# right.net
KiCad netlist of a schematic drawn in EAGLE
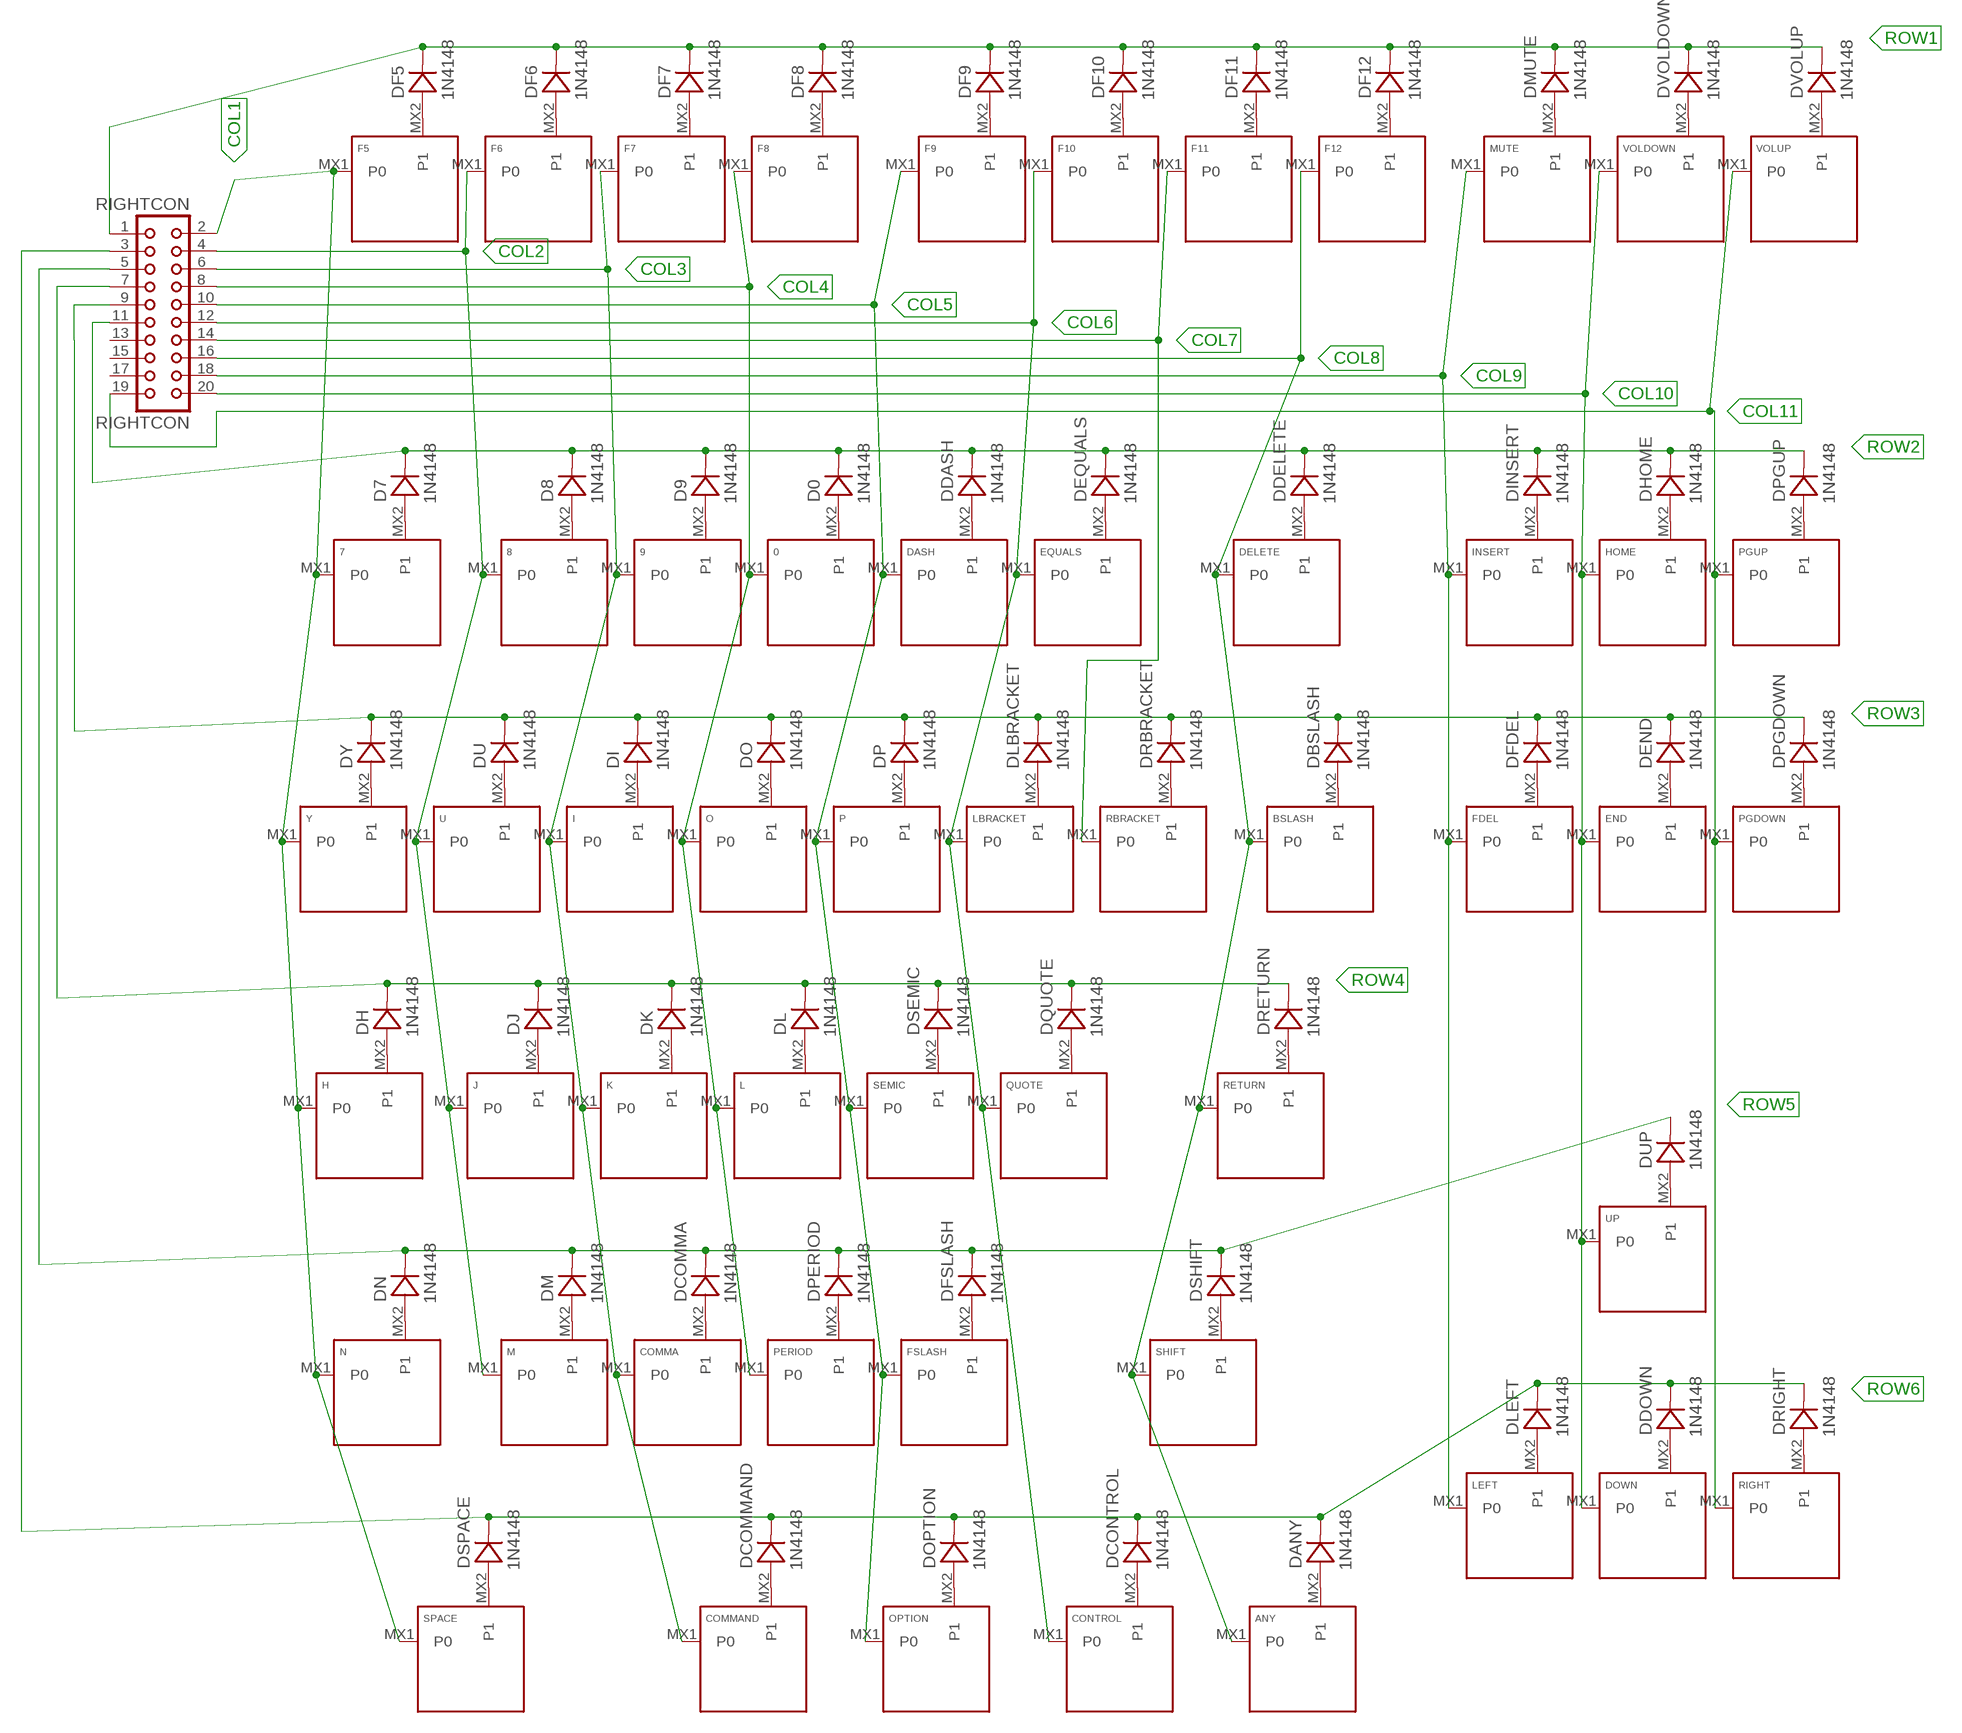
[diagram p0: schematic, sheet 1]

(export (version "E")
  (design (tool "Eeschema 10.0.6"))
  (components
    (comp (ref "0")
      (value "KEYSWITCH-PLAIN-MX-1U")
      (footprint "eagle-import:MX-1U")
      (libsource (lib "eagle-import") (part "KEYSWITCH-PLAIN-MX-1U"))
    )
    (comp (ref "7")
      (value "KEYSWITCH-PLAIN-MX-1U")
      (footprint "eagle-import:MX-1U")
      (libsource (lib "eagle-import") (part "KEYSWITCH-PLAIN-MX-1U"))
    )
    (comp (ref "8")
      (value "KEYSWITCH-PLAIN-MX-1U")
      (footprint "eagle-import:MX-1U")
      (libsource (lib "eagle-import") (part "KEYSWITCH-PLAIN-MX-1U"))
    )
    (comp (ref "9")
      (value "KEYSWITCH-PLAIN-MX-1U")
      (footprint "eagle-import:MX-1U")
      (libsource (lib "eagle-import") (part "KEYSWITCH-PLAIN-MX-1U"))
    )
    (comp (ref "ANY")
      (value "KEYSWITCH-PLAIN-MX-1U")
      (footprint "eagle-import:MX-1U")
      (libsource (lib "eagle-import") (part "KEYSWITCH-PLAIN-MX-1U"))
    )
    (comp (ref "BSLASH")
      (value "KEYSWITCH-PLAIN-MX-1U")
      (footprint "eagle-import:MX-1U")
      (libsource (lib "eagle-import") (part "KEYSWITCH-PLAIN-MX-1U"))
    )
    (comp (ref "COMMA")
      (value "KEYSWITCH-PLAIN-MX-1U")
      (footprint "eagle-import:MX-1U")
      (libsource (lib "eagle-import") (part "KEYSWITCH-PLAIN-MX-1U"))
    )
    (comp (ref "COMMAND")
      (value "KEYSWITCH-PLAIN-MX-1U")
      (footprint "eagle-import:MX-1U")
      (libsource (lib "eagle-import") (part "KEYSWITCH-PLAIN-MX-1U"))
    )
    (comp (ref "CONTROL")
      (value "KEYSWITCH-PLAIN-MX-1U")
      (footprint "eagle-import:MX-1U")
      (libsource (lib "eagle-import") (part "KEYSWITCH-PLAIN-MX-1U"))
    )
    (comp (ref "D0")
      (value "1N4148")
      (footprint "eagle-import:DO-35")
      (libsource (lib "eagle-import") (part "DIODE-DO-35"))
    )
    (comp (ref "D7")
      (value "1N4148")
      (footprint "eagle-import:DO-35")
      (libsource (lib "eagle-import") (part "DIODE-DO-35"))
    )
    (comp (ref "D8")
      (value "1N4148")
      (footprint "eagle-import:DO-35")
      (libsource (lib "eagle-import") (part "DIODE-DO-35"))
    )
    (comp (ref "D9")
      (value "1N4148")
      (footprint "eagle-import:DO-35")
      (libsource (lib "eagle-import") (part "DIODE-DO-35"))
    )
    (comp (ref "DANY")
      (value "1N4148")
      (footprint "eagle-import:DO-35")
      (libsource (lib "eagle-import") (part "DIODE-DO-35"))
    )
    (comp (ref "DASH")
      (value "KEYSWITCH-PLAIN-MX-1U")
      (footprint "eagle-import:MX-1U")
      (libsource (lib "eagle-import") (part "KEYSWITCH-PLAIN-MX-1U"))
    )
    (comp (ref "DBSLASH")
      (value "1N4148")
      (footprint "eagle-import:DO-35")
      (libsource (lib "eagle-import") (part "DIODE-DO-35"))
    )
    (comp (ref "DCOMMA")
      (value "1N4148")
      (footprint "eagle-import:DO-35")
      (libsource (lib "eagle-import") (part "DIODE-DO-35"))
    )
    (comp (ref "DCOMMAND")
      (value "1N4148")
      (footprint "eagle-import:DO-35")
      (libsource (lib "eagle-import") (part "DIODE-DO-35"))
    )
    (comp (ref "DCONTROL")
      (value "1N4148")
      (footprint "eagle-import:DO-35")
      (libsource (lib "eagle-import") (part "DIODE-DO-35"))
    )
    (comp (ref "DDASH")
      (value "1N4148")
      (footprint "eagle-import:DO-35")
      (libsource (lib "eagle-import") (part "DIODE-DO-35"))
    )
    (comp (ref "DDELETE")
      (value "1N4148")
      (footprint "eagle-import:DO-35")
      (libsource (lib "eagle-import") (part "DIODE-DO-35"))
    )
    (comp (ref "DDOWN")
      (value "1N4148")
      (footprint "eagle-import:DO-35")
      (libsource (lib "eagle-import") (part "DIODE-DO-35"))
    )
    (comp (ref "DELETE")
      (value "KEYSWITCH-PLAIN-MX-2U")
      (footprint "eagle-import:MX-2U")
      (libsource (lib "eagle-import") (part "KEYSWITCH-PLAIN-MX-2U"))
    )
    (comp (ref "DEND")
      (value "1N4148")
      (footprint "eagle-import:DO-35")
      (libsource (lib "eagle-import") (part "DIODE-DO-35"))
    )
    (comp (ref "DEQUALS")
      (value "1N4148")
      (footprint "eagle-import:DO-35")
      (libsource (lib "eagle-import") (part "DIODE-DO-35"))
    )
    (comp (ref "DF5")
      (value "1N4148")
      (footprint "eagle-import:DO-35")
      (libsource (lib "eagle-import") (part "DIODE-DO-35"))
    )
    (comp (ref "DF6")
      (value "1N4148")
      (footprint "eagle-import:DO-35")
      (libsource (lib "eagle-import") (part "DIODE-DO-35"))
    )
    (comp (ref "DF7")
      (value "1N4148")
      (footprint "eagle-import:DO-35")
      (libsource (lib "eagle-import") (part "DIODE-DO-35"))
    )
    (comp (ref "DF8")
      (value "1N4148")
      (footprint "eagle-import:DO-35")
      (libsource (lib "eagle-import") (part "DIODE-DO-35"))
    )
    (comp (ref "DF9")
      (value "1N4148")
      (footprint "eagle-import:DO-35")
      (libsource (lib "eagle-import") (part "DIODE-DO-35"))
    )
    (comp (ref "DF10")
      (value "1N4148")
      (footprint "eagle-import:DO-35")
      (libsource (lib "eagle-import") (part "DIODE-DO-35"))
    )
    (comp (ref "DF11")
      (value "1N4148")
      (footprint "eagle-import:DO-35")
      (libsource (lib "eagle-import") (part "DIODE-DO-35"))
    )
    (comp (ref "DF12")
      (value "1N4148")
      (footprint "eagle-import:DO-35")
      (libsource (lib "eagle-import") (part "DIODE-DO-35"))
    )
    (comp (ref "DFDEL")
      (value "1N4148")
      (footprint "eagle-import:DO-35")
      (libsource (lib "eagle-import") (part "DIODE-DO-35"))
    )
    (comp (ref "DFSLASH")
      (value "1N4148")
      (footprint "eagle-import:DO-35")
      (libsource (lib "eagle-import") (part "DIODE-DO-35"))
    )
    (comp (ref "DH")
      (value "1N4148")
      (footprint "eagle-import:DO-35")
      (libsource (lib "eagle-import") (part "DIODE-DO-35"))
    )
    (comp (ref "DHOME")
      (value "1N4148")
      (footprint "eagle-import:DO-35")
      (libsource (lib "eagle-import") (part "DIODE-DO-35"))
    )
    (comp (ref "DI")
      (value "1N4148")
      (footprint "eagle-import:DO-35")
      (libsource (lib "eagle-import") (part "DIODE-DO-35"))
    )
    (comp (ref "DINSERT")
      (value "1N4148")
      (footprint "eagle-import:DO-35")
      (libsource (lib "eagle-import") (part "DIODE-DO-35"))
    )
    (comp (ref "DJ")
      (value "1N4148")
      (footprint "eagle-import:DO-35")
      (libsource (lib "eagle-import") (part "DIODE-DO-35"))
    )
    (comp (ref "DK")
      (value "1N4148")
      (footprint "eagle-import:DO-35")
      (libsource (lib "eagle-import") (part "DIODE-DO-35"))
    )
    (comp (ref "DL")
      (value "1N4148")
      (footprint "eagle-import:DO-35")
      (libsource (lib "eagle-import") (part "DIODE-DO-35"))
    )
    (comp (ref "DLBRACKET")
      (value "1N4148")
      (footprint "eagle-import:DO-35")
      (libsource (lib "eagle-import") (part "DIODE-DO-35"))
    )
    (comp (ref "DLEFT")
      (value "1N4148")
      (footprint "eagle-import:DO-35")
      (libsource (lib "eagle-import") (part "DIODE-DO-35"))
    )
    (comp (ref "DM")
      (value "1N4148")
      (footprint "eagle-import:DO-35")
      (libsource (lib "eagle-import") (part "DIODE-DO-35"))
    )
    (comp (ref "DMUTE")
      (value "1N4148")
      (footprint "eagle-import:DO-35")
      (libsource (lib "eagle-import") (part "DIODE-DO-35"))
    )
    (comp (ref "DN")
      (value "1N4148")
      (footprint "eagle-import:DO-35")
      (libsource (lib "eagle-import") (part "DIODE-DO-35"))
    )
    (comp (ref "DO")
      (value "1N4148")
      (footprint "eagle-import:DO-35")
      (libsource (lib "eagle-import") (part "DIODE-DO-35"))
    )
    (comp (ref "DOPTION")
      (value "1N4148")
      (footprint "eagle-import:DO-35")
      (libsource (lib "eagle-import") (part "DIODE-DO-35"))
    )
    (comp (ref "DOWN")
      (value "KEYSWITCH-PLAIN-MX-1U")
      (footprint "eagle-import:MX-1U")
      (libsource (lib "eagle-import") (part "KEYSWITCH-PLAIN-MX-1U"))
    )
    (comp (ref "DP")
      (value "1N4148")
      (footprint "eagle-import:DO-35")
      (libsource (lib "eagle-import") (part "DIODE-DO-35"))
    )
    (comp (ref "DPERIOD")
      (value "1N4148")
      (footprint "eagle-import:DO-35")
      (libsource (lib "eagle-import") (part "DIODE-DO-35"))
    )
    (comp (ref "DPGDOWN")
      (value "1N4148")
      (footprint "eagle-import:DO-35")
      (libsource (lib "eagle-import") (part "DIODE-DO-35"))
    )
    (comp (ref "DPGUP")
      (value "1N4148")
      (footprint "eagle-import:DO-35")
      (libsource (lib "eagle-import") (part "DIODE-DO-35"))
    )
    (comp (ref "DQUOTE")
      (value "1N4148")
      (footprint "eagle-import:DO-35")
      (libsource (lib "eagle-import") (part "DIODE-DO-35"))
    )
    (comp (ref "DRBRACKET")
      (value "1N4148")
      (footprint "eagle-import:DO-35")
      (libsource (lib "eagle-import") (part "DIODE-DO-35"))
    )
    (comp (ref "DRETURN")
      (value "1N4148")
      (footprint "eagle-import:DO-35")
      (libsource (lib "eagle-import") (part "DIODE-DO-35"))
    )
    (comp (ref "DRIGHT")
      (value "1N4148")
      (footprint "eagle-import:DO-35")
      (libsource (lib "eagle-import") (part "DIODE-DO-35"))
    )
    (comp (ref "DSEMIC")
      (value "1N4148")
      (footprint "eagle-import:DO-35")
      (libsource (lib "eagle-import") (part "DIODE-DO-35"))
    )
    (comp (ref "DSHIFT")
      (value "1N4148")
      (footprint "eagle-import:DO-35")
      (libsource (lib "eagle-import") (part "DIODE-DO-35"))
    )
    (comp (ref "DSPACE")
      (value "1N4148")
      (footprint "eagle-import:DO-35")
      (libsource (lib "eagle-import") (part "DIODE-DO-35"))
    )
    (comp (ref "DU")
      (value "1N4148")
      (footprint "eagle-import:DO-35")
      (libsource (lib "eagle-import") (part "DIODE-DO-35"))
    )
    (comp (ref "DUP")
      (value "1N4148")
      (footprint "eagle-import:DO-35")
      (libsource (lib "eagle-import") (part "DIODE-DO-35"))
    )
    (comp (ref "DVOLDOWN")
      (value "1N4148")
      (footprint "eagle-import:DO-35")
      (libsource (lib "eagle-import") (part "DIODE-DO-35"))
    )
    (comp (ref "DVOLUP")
      (value "1N4148")
      (footprint "eagle-import:DO-35")
      (libsource (lib "eagle-import") (part "DIODE-DO-35"))
    )
    (comp (ref "DY")
      (value "1N4148")
      (footprint "eagle-import:DO-35")
      (libsource (lib "eagle-import") (part "DIODE-DO-35"))
    )
    (comp (ref "END")
      (value "KEYSWITCH-PLAIN-MX-1U")
      (footprint "eagle-import:MX-1U")
      (libsource (lib "eagle-import") (part "KEYSWITCH-PLAIN-MX-1U"))
    )
    (comp (ref "EQUALS")
      (value "KEYSWITCH-PLAIN-MX-1U")
      (footprint "eagle-import:MX-1U")
      (libsource (lib "eagle-import") (part "KEYSWITCH-PLAIN-MX-1U"))
    )
    (comp (ref "F5")
      (value "KEYSWITCH-PLAIN-MX-1U")
      (footprint "eagle-import:MX-1U")
      (libsource (lib "eagle-import") (part "KEYSWITCH-PLAIN-MX-1U"))
    )
    (comp (ref "F6")
      (value "KEYSWITCH-PLAIN-MX-1U")
      (footprint "eagle-import:MX-1U")
      (libsource (lib "eagle-import") (part "KEYSWITCH-PLAIN-MX-1U"))
    )
    (comp (ref "F7")
      (value "KEYSWITCH-PLAIN-MX-1U")
      (footprint "eagle-import:MX-1U")
      (libsource (lib "eagle-import") (part "KEYSWITCH-PLAIN-MX-1U"))
    )
    (comp (ref "F8")
      (value "KEYSWITCH-PLAIN-MX-1U")
      (footprint "eagle-import:MX-1U")
      (libsource (lib "eagle-import") (part "KEYSWITCH-PLAIN-MX-1U"))
    )
    (comp (ref "F9")
      (value "KEYSWITCH-PLAIN-MX-1U")
      (footprint "eagle-import:MX-1U")
      (libsource (lib "eagle-import") (part "KEYSWITCH-PLAIN-MX-1U"))
    )
    (comp (ref "F10")
      (value "KEYSWITCH-PLAIN-MX-1U")
      (footprint "eagle-import:MX-1U")
      (libsource (lib "eagle-import") (part "KEYSWITCH-PLAIN-MX-1U"))
    )
    (comp (ref "F11")
      (value "KEYSWITCH-PLAIN-MX-1U")
      (footprint "eagle-import:MX-1U")
      (libsource (lib "eagle-import") (part "KEYSWITCH-PLAIN-MX-1U"))
    )
    (comp (ref "F12")
      (value "KEYSWITCH-PLAIN-MX-1U")
      (footprint "eagle-import:MX-1U")
      (libsource (lib "eagle-import") (part "KEYSWITCH-PLAIN-MX-1U"))
    )
    (comp (ref "FDEL")
      (value "KEYSWITCH-PLAIN-MX-1U")
      (footprint "eagle-import:MX-1U")
      (libsource (lib "eagle-import") (part "KEYSWITCH-PLAIN-MX-1U"))
    )
    (comp (ref "FSLASH")
      (value "KEYSWITCH-PLAIN-MX-1U")
      (footprint "eagle-import:MX-1U")
      (libsource (lib "eagle-import") (part "KEYSWITCH-PLAIN-MX-1U"))
    )
    (comp (ref "H")
      (value "KEYSWITCH-PLAIN-MX-1U")
      (footprint "eagle-import:MX-1U")
      (libsource (lib "eagle-import") (part "KEYSWITCH-PLAIN-MX-1U"))
    )
    (comp (ref "HOME")
      (value "KEYSWITCH-PLAIN-MX-1U")
      (footprint "eagle-import:MX-1U")
      (libsource (lib "eagle-import") (part "KEYSWITCH-PLAIN-MX-1U"))
    )
    (comp (ref "I")
      (value "KEYSWITCH-PLAIN-MX-1U")
      (footprint "eagle-import:MX-1U")
      (libsource (lib "eagle-import") (part "KEYSWITCH-PLAIN-MX-1U"))
    )
    (comp (ref "INSERT")
      (value "KEYSWITCH-PLAIN-MX-1U")
      (footprint "eagle-import:MX-1U")
      (libsource (lib "eagle-import") (part "KEYSWITCH-PLAIN-MX-1U"))
    )
    (comp (ref "J")
      (value "KEYSWITCH-PLAIN-MX-1U")
      (footprint "eagle-import:MX-1U")
      (libsource (lib "eagle-import") (part "KEYSWITCH-PLAIN-MX-1U"))
    )
    (comp (ref "K")
      (value "KEYSWITCH-PLAIN-MX-1U")
      (footprint "eagle-import:MX-1U")
      (libsource (lib "eagle-import") (part "KEYSWITCH-PLAIN-MX-1U"))
    )
    (comp (ref "L")
      (value "KEYSWITCH-PLAIN-MX-1U")
      (footprint "eagle-import:MX-1U")
      (libsource (lib "eagle-import") (part "KEYSWITCH-PLAIN-MX-1U"))
    )
    (comp (ref "LBRACKET")
      (value "KEYSWITCH-PLAIN-MX-1U")
      (footprint "eagle-import:MX-1U")
      (libsource (lib "eagle-import") (part "KEYSWITCH-PLAIN-MX-1U"))
    )
    (comp (ref "LEFT")
      (value "KEYSWITCH-PLAIN-MX-1U")
      (footprint "eagle-import:MX-1U")
      (libsource (lib "eagle-import") (part "KEYSWITCH-PLAIN-MX-1U"))
    )
    (comp (ref "M")
      (value "KEYSWITCH-PLAIN-MX-1U")
      (footprint "eagle-import:MX-1U")
      (libsource (lib "eagle-import") (part "KEYSWITCH-PLAIN-MX-1U"))
    )
    (comp (ref "MUTE")
      (value "KEYSWITCH-PLAIN-MX-1U")
      (footprint "eagle-import:MX-1U")
      (libsource (lib "eagle-import") (part "KEYSWITCH-PLAIN-MX-1U"))
    )
    (comp (ref "N")
      (value "KEYSWITCH-PLAIN-MX-1U")
      (footprint "eagle-import:MX-1U")
      (libsource (lib "eagle-import") (part "KEYSWITCH-PLAIN-MX-1U"))
    )
    (comp (ref "O")
      (value "KEYSWITCH-PLAIN-MX-1U")
      (footprint "eagle-import:MX-1U")
      (libsource (lib "eagle-import") (part "KEYSWITCH-PLAIN-MX-1U"))
    )
    (comp (ref "OPTION")
      (value "KEYSWITCH-PLAIN-MX-1U")
      (footprint "eagle-import:MX-1U")
      (libsource (lib "eagle-import") (part "KEYSWITCH-PLAIN-MX-1U"))
    )
    (comp (ref "P")
      (value "KEYSWITCH-PLAIN-MX-1U")
      (footprint "eagle-import:MX-1U")
      (libsource (lib "eagle-import") (part "KEYSWITCH-PLAIN-MX-1U"))
    )
    (comp (ref "PERIOD")
      (value "KEYSWITCH-PLAIN-MX-1U")
      (footprint "eagle-import:MX-1U")
      (libsource (lib "eagle-import") (part "KEYSWITCH-PLAIN-MX-1U"))
    )
    (comp (ref "PGDOWN")
      (value "KEYSWITCH-PLAIN-MX-1U")
      (footprint "eagle-import:MX-1U")
      (libsource (lib "eagle-import") (part "KEYSWITCH-PLAIN-MX-1U"))
    )
    (comp (ref "PGUP")
      (value "KEYSWITCH-PLAIN-MX-1U")
      (footprint "eagle-import:MX-1U")
      (libsource (lib "eagle-import") (part "KEYSWITCH-PLAIN-MX-1U"))
    )
    (comp (ref "QUOTE")
      (value "KEYSWITCH-PLAIN-MX-1U")
      (footprint "eagle-import:MX-1U")
      (libsource (lib "eagle-import") (part "KEYSWITCH-PLAIN-MX-1U"))
    )
    (comp (ref "RBRACKET")
      (value "KEYSWITCH-PLAIN-MX-1U")
      (footprint "eagle-import:MX-1U")
      (libsource (lib "eagle-import") (part "KEYSWITCH-PLAIN-MX-1U"))
    )
    (comp (ref "RETURN")
      (value "KEYSWITCH-PLAIN-MX-2U")
      (footprint "eagle-import:MX-2U")
      (libsource (lib "eagle-import") (part "KEYSWITCH-PLAIN-MX-2U"))
    )
    (comp (ref "RIGHT")
      (value "KEYSWITCH-PLAIN-MX-1U")
      (footprint "eagle-import:MX-1U")
      (libsource (lib "eagle-import") (part "KEYSWITCH-PLAIN-MX-1U"))
    )
    (comp (ref "RIGHTCON")
      (value "RIGHTCON")
      (footprint "eagle-import:CON20")
      (libsource (lib "eagle-import") (part "CON20"))
    )
    (comp (ref "SEMIC")
      (value "KEYSWITCH-PLAIN-MX-1U")
      (footprint "eagle-import:MX-1U")
      (libsource (lib "eagle-import") (part "KEYSWITCH-PLAIN-MX-1U"))
    )
    (comp (ref "SHIFT")
      (value "KEYSWITCH-PLAIN-MX-2U")
      (footprint "eagle-import:MX-2U")
      (libsource (lib "eagle-import") (part "KEYSWITCH-PLAIN-MX-2U"))
    )
    (comp (ref "SPACE")
      (value "KEYSWITCH-PLAIN-MX-2U")
      (footprint "eagle-import:MX-2U")
      (libsource (lib "eagle-import") (part "KEYSWITCH-PLAIN-MX-2U"))
    )
    (comp (ref "U")
      (value "KEYSWITCH-PLAIN-MX-1U")
      (footprint "eagle-import:MX-1U")
      (libsource (lib "eagle-import") (part "KEYSWITCH-PLAIN-MX-1U"))
    )
    (comp (ref "UP")
      (value "KEYSWITCH-PLAIN-MX-1U")
      (footprint "eagle-import:MX-1U")
      (libsource (lib "eagle-import") (part "KEYSWITCH-PLAIN-MX-1U"))
    )
    (comp (ref "VOLDOWN")
      (value "KEYSWITCH-PLAIN-MX-1U")
      (footprint "eagle-import:MX-1U")
      (libsource (lib "eagle-import") (part "KEYSWITCH-PLAIN-MX-1U"))
    )
    (comp (ref "VOLUP")
      (value "KEYSWITCH-PLAIN-MX-1U")
      (footprint "eagle-import:MX-1U")
      (libsource (lib "eagle-import") (part "KEYSWITCH-PLAIN-MX-1U"))
    )
    (comp (ref "Y")
      (value "KEYSWITCH-PLAIN-MX-1U")
      (footprint "eagle-import:MX-1U")
      (libsource (lib "eagle-import") (part "KEYSWITCH-PLAIN-MX-1U"))
    )
  )
  (nets
    (net (code "1") (name "COL1") (class "Default")
      (node (ref "7") (pin "MX1") (pinfunction "P0_MX1") (pintype "bidirectional"))
      (node (ref "F5") (pin "MX1") (pinfunction "P0_MX1") (pintype "bidirectional"))
      (node (ref "H") (pin "MX1") (pinfunction "P0_MX1") (pintype "bidirectional"))
      (node (ref "N") (pin "MX1") (pinfunction "P0_MX1") (pintype "bidirectional"))
      (node (ref "RIGHTCON") (pin "2") (pinfunction "2_2") (pintype "passive"))
      (node (ref "SPACE") (pin "MX1") (pinfunction "P0_MX1") (pintype "bidirectional"))
      (node (ref "Y") (pin "MX1") (pinfunction "P0_MX1") (pintype "bidirectional"))
    )
    (net (code "2") (name "COL2") (class "Default")
      (node (ref "8") (pin "MX1") (pinfunction "P0_MX1") (pintype "bidirectional"))
      (node (ref "F6") (pin "MX1") (pinfunction "P0_MX1") (pintype "bidirectional"))
      (node (ref "J") (pin "MX1") (pinfunction "P0_MX1") (pintype "bidirectional"))
      (node (ref "M") (pin "MX1") (pinfunction "P0_MX1") (pintype "bidirectional"))
      (node (ref "RIGHTCON") (pin "4") (pinfunction "4_4") (pintype "passive"))
      (node (ref "U") (pin "MX1") (pinfunction "P0_MX1") (pintype "bidirectional"))
    )
    (net (code "3") (name "COL3") (class "Default")
      (node (ref "9") (pin "MX1") (pinfunction "P0_MX1") (pintype "bidirectional"))
      (node (ref "COMMA") (pin "MX1") (pinfunction "P0_MX1") (pintype "bidirectional"))
      (node (ref "COMMAND") (pin "MX1") (pinfunction "P0_MX1") (pintype "bidirectional"))
      (node (ref "F7") (pin "MX1") (pinfunction "P0_MX1") (pintype "bidirectional"))
      (node (ref "I") (pin "MX1") (pinfunction "P0_MX1") (pintype "bidirectional"))
      (node (ref "K") (pin "MX1") (pinfunction "P0_MX1") (pintype "bidirectional"))
      (node (ref "RIGHTCON") (pin "6") (pinfunction "6_6") (pintype "passive"))
    )
    (net (code "4") (name "COL4") (class "Default")
      (node (ref "0") (pin "MX1") (pinfunction "P0_MX1") (pintype "bidirectional"))
      (node (ref "F8") (pin "MX1") (pinfunction "P0_MX1") (pintype "bidirectional"))
      (node (ref "L") (pin "MX1") (pinfunction "P0_MX1") (pintype "bidirectional"))
      (node (ref "O") (pin "MX1") (pinfunction "P0_MX1") (pintype "bidirectional"))
      (node (ref "PERIOD") (pin "MX1") (pinfunction "P0_MX1") (pintype "bidirectional"))
      (node (ref "RIGHTCON") (pin "8") (pinfunction "8_8") (pintype "passive"))
    )
    (net (code "5") (name "COL5") (class "Default")
      (node (ref "DASH") (pin "MX1") (pinfunction "P0_MX1") (pintype "bidirectional"))
      (node (ref "F9") (pin "MX1") (pinfunction "P0_MX1") (pintype "bidirectional"))
      (node (ref "FSLASH") (pin "MX1") (pinfunction "P0_MX1") (pintype "bidirectional"))
      (node (ref "OPTION") (pin "MX1") (pinfunction "P0_MX1") (pintype "bidirectional"))
      (node (ref "P") (pin "MX1") (pinfunction "P0_MX1") (pintype "bidirectional"))
      (node (ref "RIGHTCON") (pin "10") (pinfunction "10_10") (pintype "passive"))
      (node (ref "SEMIC") (pin "MX1") (pinfunction "P0_MX1") (pintype "bidirectional"))
    )
    (net (code "6") (name "COL6") (class "Default")
      (node (ref "CONTROL") (pin "MX1") (pinfunction "P0_MX1") (pintype "bidirectional"))
      (node (ref "EQUALS") (pin "MX1") (pinfunction "P0_MX1") (pintype "bidirectional"))
      (node (ref "F10") (pin "MX1") (pinfunction "P0_MX1") (pintype "bidirectional"))
      (node (ref "LBRACKET") (pin "MX1") (pinfunction "P0_MX1") (pintype "bidirectional"))
      (node (ref "QUOTE") (pin "MX1") (pinfunction "P0_MX1") (pintype "bidirectional"))
      (node (ref "RIGHTCON") (pin "12") (pinfunction "12_12") (pintype "passive"))
    )
    (net (code "7") (name "COL7") (class "Default")
      (node (ref "F11") (pin "MX1") (pinfunction "P0_MX1") (pintype "bidirectional"))
      (node (ref "RBRACKET") (pin "MX1") (pinfunction "P0_MX1") (pintype "bidirectional"))
      (node (ref "RIGHTCON") (pin "14") (pinfunction "14_14") (pintype "passive"))
    )
    (net (code "8") (name "COL8") (class "Default")
      (node (ref "ANY") (pin "MX1") (pinfunction "P0_MX1") (pintype "bidirectional"))
      (node (ref "BSLASH") (pin "MX1") (pinfunction "P0_MX1") (pintype "bidirectional"))
      (node (ref "DELETE") (pin "MX1") (pinfunction "P0_MX1") (pintype "bidirectional"))
      (node (ref "F12") (pin "MX1") (pinfunction "P0_MX1") (pintype "bidirectional"))
      (node (ref "RETURN") (pin "MX1") (pinfunction "P0_MX1") (pintype "bidirectional"))
      (node (ref "RIGHTCON") (pin "16") (pinfunction "16_16") (pintype "passive"))
      (node (ref "SHIFT") (pin "MX1") (pinfunction "P0_MX1") (pintype "bidirectional"))
    )
    (net (code "9") (name "COL9") (class "Default")
      (node (ref "FDEL") (pin "MX1") (pinfunction "P0_MX1") (pintype "bidirectional"))
      (node (ref "INSERT") (pin "MX1") (pinfunction "P0_MX1") (pintype "bidirectional"))
      (node (ref "LEFT") (pin "MX1") (pinfunction "P0_MX1") (pintype "bidirectional"))
      (node (ref "MUTE") (pin "MX1") (pinfunction "P0_MX1") (pintype "bidirectional"))
      (node (ref "RIGHTCON") (pin "18") (pinfunction "18_18") (pintype "passive"))
    )
    (net (code "10") (name "COL10") (class "Default")
      (node (ref "DOWN") (pin "MX1") (pinfunction "P0_MX1") (pintype "bidirectional"))
      (node (ref "END") (pin "MX1") (pinfunction "P0_MX1") (pintype "bidirectional"))
      (node (ref "HOME") (pin "MX1") (pinfunction "P0_MX1") (pintype "bidirectional"))
      (node (ref "RIGHTCON") (pin "20") (pinfunction "20_20") (pintype "passive"))
      (node (ref "UP") (pin "MX1") (pinfunction "P0_MX1") (pintype "bidirectional"))
      (node (ref "VOLDOWN") (pin "MX1") (pinfunction "P0_MX1") (pintype "bidirectional"))
    )
    (net (code "11") (name "COL11") (class "Default")
      (node (ref "PGDOWN") (pin "MX1") (pinfunction "P0_MX1") (pintype "bidirectional"))
      (node (ref "PGUP") (pin "MX1") (pinfunction "P0_MX1") (pintype "bidirectional"))
      (node (ref "RIGHT") (pin "MX1") (pinfunction "P0_MX1") (pintype "bidirectional"))
      (node (ref "RIGHTCON") (pin "19") (pinfunction "19_19") (pintype "passive"))
      (node (ref "VOLUP") (pin "MX1") (pinfunction "P0_MX1") (pintype "bidirectional"))
    )
    (net (code "12") (name "Net-(0-P1)") (class "Default")
      (node (ref "0") (pin "MX2") (pinfunction "P1_MX2") (pintype "bidirectional"))
      (node (ref "D0") (pin "A") (pinfunction "A_A") (pintype "passive"))
    )
    (net (code "13") (name "Net-(7-P1)") (class "Default")
      (node (ref "7") (pin "MX2") (pinfunction "P1_MX2") (pintype "bidirectional"))
      (node (ref "D7") (pin "A") (pinfunction "A_A") (pintype "passive"))
    )
    (net (code "14") (name "Net-(8-P1)") (class "Default")
      (node (ref "8") (pin "MX2") (pinfunction "P1_MX2") (pintype "bidirectional"))
      (node (ref "D8") (pin "A") (pinfunction "A_A") (pintype "passive"))
    )
    (net (code "15") (name "Net-(9-P1)") (class "Default")
      (node (ref "9") (pin "MX2") (pinfunction "P1_MX2") (pintype "bidirectional"))
      (node (ref "D9") (pin "A") (pinfunction "A_A") (pintype "passive"))
    )
    (net (code "16") (name "Net-(ANY-P1)") (class "Default")
      (node (ref "ANY") (pin "MX2") (pinfunction "P1_MX2") (pintype "bidirectional"))
      (node (ref "DANY") (pin "A") (pinfunction "A_A") (pintype "passive"))
    )
    (net (code "17") (name "Net-(BSLASH-P1)") (class "Default")
      (node (ref "BSLASH") (pin "MX2") (pinfunction "P1_MX2") (pintype "bidirectional"))
      (node (ref "DBSLASH") (pin "A") (pinfunction "A_A") (pintype "passive"))
    )
    (net (code "18") (name "Net-(COMMA-P1)") (class "Default")
      (node (ref "COMMA") (pin "MX2") (pinfunction "P1_MX2") (pintype "bidirectional"))
      (node (ref "DCOMMA") (pin "A") (pinfunction "A_A") (pintype "passive"))
    )
    (net (code "19") (name "Net-(COMMAND-P1)") (class "Default")
      (node (ref "COMMAND") (pin "MX2") (pinfunction "P1_MX2") (pintype "bidirectional"))
      (node (ref "DCOMMAND") (pin "A") (pinfunction "A_A") (pintype "passive"))
    )
    (net (code "20") (name "Net-(CONTROL-P1)") (class "Default")
      (node (ref "CONTROL") (pin "MX2") (pinfunction "P1_MX2") (pintype "bidirectional"))
      (node (ref "DCONTROL") (pin "A") (pinfunction "A_A") (pintype "passive"))
    )
    (net (code "21") (name "Net-(DASH-P1)") (class "Default")
      (node (ref "DASH") (pin "MX2") (pinfunction "P1_MX2") (pintype "bidirectional"))
      (node (ref "DDASH") (pin "A") (pinfunction "A_A") (pintype "passive"))
    )
    (net (code "22") (name "Net-(DELETE-P1)") (class "Default")
      (node (ref "DDELETE") (pin "A") (pinfunction "A_A") (pintype "passive"))
      (node (ref "DELETE") (pin "MX2") (pinfunction "P1_MX2") (pintype "bidirectional"))
    )
    (net (code "23") (name "Net-(DOWN-P1)") (class "Default")
      (node (ref "DDOWN") (pin "A") (pinfunction "A_A") (pintype "passive"))
      (node (ref "DOWN") (pin "MX2") (pinfunction "P1_MX2") (pintype "bidirectional"))
    )
    (net (code "24") (name "Net-(END-P1)") (class "Default")
      (node (ref "DEND") (pin "A") (pinfunction "A_A") (pintype "passive"))
      (node (ref "END") (pin "MX2") (pinfunction "P1_MX2") (pintype "bidirectional"))
    )
    (net (code "25") (name "Net-(EQUALS-P1)") (class "Default")
      (node (ref "DEQUALS") (pin "A") (pinfunction "A_A") (pintype "passive"))
      (node (ref "EQUALS") (pin "MX2") (pinfunction "P1_MX2") (pintype "bidirectional"))
    )
    (net (code "26") (name "Net-(F5-P1)") (class "Default")
      (node (ref "DF5") (pin "A") (pinfunction "A_A") (pintype "passive"))
      (node (ref "F5") (pin "MX2") (pinfunction "P1_MX2") (pintype "bidirectional"))
    )
    (net (code "27") (name "Net-(F6-P1)") (class "Default")
      (node (ref "DF6") (pin "A") (pinfunction "A_A") (pintype "passive"))
      (node (ref "F6") (pin "MX2") (pinfunction "P1_MX2") (pintype "bidirectional"))
    )
    (net (code "28") (name "Net-(F7-P1)") (class "Default")
      (node (ref "DF7") (pin "A") (pinfunction "A_A") (pintype "passive"))
      (node (ref "F7") (pin "MX2") (pinfunction "P1_MX2") (pintype "bidirectional"))
    )
    (net (code "29") (name "Net-(F8-P1)") (class "Default")
      (node (ref "DF8") (pin "A") (pinfunction "A_A") (pintype "passive"))
      (node (ref "F8") (pin "MX2") (pinfunction "P1_MX2") (pintype "bidirectional"))
    )
    (net (code "30") (name "Net-(F9-P1)") (class "Default")
      (node (ref "DF9") (pin "A") (pinfunction "A_A") (pintype "passive"))
      (node (ref "F9") (pin "MX2") (pinfunction "P1_MX2") (pintype "bidirectional"))
    )
    (net (code "31") (name "Net-(F10-P1)") (class "Default")
      (node (ref "DF10") (pin "A") (pinfunction "A_A") (pintype "passive"))
      (node (ref "F10") (pin "MX2") (pinfunction "P1_MX2") (pintype "bidirectional"))
    )
    (net (code "32") (name "Net-(F11-P1)") (class "Default")
      (node (ref "DF11") (pin "A") (pinfunction "A_A") (pintype "passive"))
      (node (ref "F11") (pin "MX2") (pinfunction "P1_MX2") (pintype "bidirectional"))
    )
    (net (code "33") (name "Net-(F12-P1)") (class "Default")
      (node (ref "DF12") (pin "A") (pinfunction "A_A") (pintype "passive"))
      (node (ref "F12") (pin "MX2") (pinfunction "P1_MX2") (pintype "bidirectional"))
    )
    (net (code "34") (name "Net-(FDEL-P1)") (class "Default")
      (node (ref "DFDEL") (pin "A") (pinfunction "A_A") (pintype "passive"))
      (node (ref "FDEL") (pin "MX2") (pinfunction "P1_MX2") (pintype "bidirectional"))
    )
    (net (code "35") (name "Net-(FSLASH-P1)") (class "Default")
      (node (ref "DFSLASH") (pin "A") (pinfunction "A_A") (pintype "passive"))
      (node (ref "FSLASH") (pin "MX2") (pinfunction "P1_MX2") (pintype "bidirectional"))
    )
    (net (code "36") (name "Net-(H-P1)") (class "Default")
      (node (ref "DH") (pin "A") (pinfunction "A_A") (pintype "passive"))
      (node (ref "H") (pin "MX2") (pinfunction "P1_MX2") (pintype "bidirectional"))
    )
    (net (code "37") (name "Net-(HOME-P1)") (class "Default")
      (node (ref "DHOME") (pin "A") (pinfunction "A_A") (pintype "passive"))
      (node (ref "HOME") (pin "MX2") (pinfunction "P1_MX2") (pintype "bidirectional"))
    )
    (net (code "38") (name "Net-(I-P1)") (class "Default")
      (node (ref "DI") (pin "A") (pinfunction "A_A") (pintype "passive"))
      (node (ref "I") (pin "MX2") (pinfunction "P1_MX2") (pintype "bidirectional"))
    )
    (net (code "39") (name "Net-(INSERT-P1)") (class "Default")
      (node (ref "DINSERT") (pin "A") (pinfunction "A_A") (pintype "passive"))
      (node (ref "INSERT") (pin "MX2") (pinfunction "P1_MX2") (pintype "bidirectional"))
    )
    (net (code "40") (name "Net-(J-P1)") (class "Default")
      (node (ref "DJ") (pin "A") (pinfunction "A_A") (pintype "passive"))
      (node (ref "J") (pin "MX2") (pinfunction "P1_MX2") (pintype "bidirectional"))
    )
    (net (code "41") (name "Net-(K-P1)") (class "Default")
      (node (ref "DK") (pin "A") (pinfunction "A_A") (pintype "passive"))
      (node (ref "K") (pin "MX2") (pinfunction "P1_MX2") (pintype "bidirectional"))
    )
    (net (code "42") (name "Net-(L-P1)") (class "Default")
      (node (ref "DL") (pin "A") (pinfunction "A_A") (pintype "passive"))
      (node (ref "L") (pin "MX2") (pinfunction "P1_MX2") (pintype "bidirectional"))
    )
    (net (code "43") (name "Net-(LBRACKET-P1)") (class "Default")
      (node (ref "DLBRACKET") (pin "A") (pinfunction "A_A") (pintype "passive"))
      (node (ref "LBRACKET") (pin "MX2") (pinfunction "P1_MX2") (pintype "bidirectional"))
    )
    (net (code "44") (name "Net-(LEFT-P1)") (class "Default")
      (node (ref "DLEFT") (pin "A") (pinfunction "A_A") (pintype "passive"))
      (node (ref "LEFT") (pin "MX2") (pinfunction "P1_MX2") (pintype "bidirectional"))
    )
    (net (code "45") (name "Net-(M-P1)") (class "Default")
      (node (ref "DM") (pin "A") (pinfunction "A_A") (pintype "passive"))
      (node (ref "M") (pin "MX2") (pinfunction "P1_MX2") (pintype "bidirectional"))
    )
    (net (code "46") (name "Net-(MUTE-P1)") (class "Default")
      (node (ref "DMUTE") (pin "A") (pinfunction "A_A") (pintype "passive"))
      (node (ref "MUTE") (pin "MX2") (pinfunction "P1_MX2") (pintype "bidirectional"))
    )
    (net (code "47") (name "Net-(N-P1)") (class "Default")
      (node (ref "DN") (pin "A") (pinfunction "A_A") (pintype "passive"))
      (node (ref "N") (pin "MX2") (pinfunction "P1_MX2") (pintype "bidirectional"))
    )
    (net (code "48") (name "Net-(O-P1)") (class "Default")
      (node (ref "DO") (pin "A") (pinfunction "A_A") (pintype "passive"))
      (node (ref "O") (pin "MX2") (pinfunction "P1_MX2") (pintype "bidirectional"))
    )
    (net (code "49") (name "Net-(OPTION-P1)") (class "Default")
      (node (ref "DOPTION") (pin "A") (pinfunction "A_A") (pintype "passive"))
      (node (ref "OPTION") (pin "MX2") (pinfunction "P1_MX2") (pintype "bidirectional"))
    )
    (net (code "50") (name "Net-(P-P1)") (class "Default")
      (node (ref "DP") (pin "A") (pinfunction "A_A") (pintype "passive"))
      (node (ref "P") (pin "MX2") (pinfunction "P1_MX2") (pintype "bidirectional"))
    )
    (net (code "51") (name "Net-(PERIOD-P1)") (class "Default")
      (node (ref "DPERIOD") (pin "A") (pinfunction "A_A") (pintype "passive"))
      (node (ref "PERIOD") (pin "MX2") (pinfunction "P1_MX2") (pintype "bidirectional"))
    )
    (net (code "52") (name "Net-(PGDOWN-P1)") (class "Default")
      (node (ref "DPGDOWN") (pin "A") (pinfunction "A_A") (pintype "passive"))
      (node (ref "PGDOWN") (pin "MX2") (pinfunction "P1_MX2") (pintype "bidirectional"))
    )
    (net (code "53") (name "Net-(PGUP-P1)") (class "Default")
      (node (ref "DPGUP") (pin "A") (pinfunction "A_A") (pintype "passive"))
      (node (ref "PGUP") (pin "MX2") (pinfunction "P1_MX2") (pintype "bidirectional"))
    )
    (net (code "54") (name "Net-(QUOTE-P1)") (class "Default")
      (node (ref "DQUOTE") (pin "A") (pinfunction "A_A") (pintype "passive"))
      (node (ref "QUOTE") (pin "MX2") (pinfunction "P1_MX2") (pintype "bidirectional"))
    )
    (net (code "55") (name "Net-(RBRACKET-P1)") (class "Default")
      (node (ref "DRBRACKET") (pin "A") (pinfunction "A_A") (pintype "passive"))
      (node (ref "RBRACKET") (pin "MX2") (pinfunction "P1_MX2") (pintype "bidirectional"))
    )
    (net (code "56") (name "Net-(RETURN-P1)") (class "Default")
      (node (ref "DRETURN") (pin "A") (pinfunction "A_A") (pintype "passive"))
      (node (ref "RETURN") (pin "MX2") (pinfunction "P1_MX2") (pintype "bidirectional"))
    )
    (net (code "57") (name "Net-(RIGHT-P1)") (class "Default")
      (node (ref "DRIGHT") (pin "A") (pinfunction "A_A") (pintype "passive"))
      (node (ref "RIGHT") (pin "MX2") (pinfunction "P1_MX2") (pintype "bidirectional"))
    )
    (net (code "58") (name "Net-(SEMIC-P1)") (class "Default")
      (node (ref "DSEMIC") (pin "A") (pinfunction "A_A") (pintype "passive"))
      (node (ref "SEMIC") (pin "MX2") (pinfunction "P1_MX2") (pintype "bidirectional"))
    )
    (net (code "59") (name "Net-(SHIFT-P1)") (class "Default")
      (node (ref "DSHIFT") (pin "A") (pinfunction "A_A") (pintype "passive"))
      (node (ref "SHIFT") (pin "MX2") (pinfunction "P1_MX2") (pintype "bidirectional"))
    )
    (net (code "60") (name "Net-(SPACE-P1)") (class "Default")
      (node (ref "DSPACE") (pin "A") (pinfunction "A_A") (pintype "passive"))
      (node (ref "SPACE") (pin "MX2") (pinfunction "P1_MX2") (pintype "bidirectional"))
    )
    (net (code "61") (name "Net-(U-P1)") (class "Default")
      (node (ref "DU") (pin "A") (pinfunction "A_A") (pintype "passive"))
      (node (ref "U") (pin "MX2") (pinfunction "P1_MX2") (pintype "bidirectional"))
    )
    (net (code "62") (name "Net-(UP-P1)") (class "Default")
      (node (ref "DUP") (pin "A") (pinfunction "A_A") (pintype "passive"))
      (node (ref "UP") (pin "MX2") (pinfunction "P1_MX2") (pintype "bidirectional"))
    )
    (net (code "63") (name "Net-(VOLDOWN-P1)") (class "Default")
      (node (ref "DVOLDOWN") (pin "A") (pinfunction "A_A") (pintype "passive"))
      (node (ref "VOLDOWN") (pin "MX2") (pinfunction "P1_MX2") (pintype "bidirectional"))
    )
    (net (code "64") (name "Net-(VOLUP-P1)") (class "Default")
      (node (ref "DVOLUP") (pin "A") (pinfunction "A_A") (pintype "passive"))
      (node (ref "VOLUP") (pin "MX2") (pinfunction "P1_MX2") (pintype "bidirectional"))
    )
    (net (code "65") (name "Net-(Y-P1)") (class "Default")
      (node (ref "DY") (pin "A") (pinfunction "A_A") (pintype "passive"))
      (node (ref "Y") (pin "MX2") (pinfunction "P1_MX2") (pintype "bidirectional"))
    )
    (net (code "66") (name "ROW1") (class "Default")
      (node (ref "DF10") (pin "C") (pinfunction "C_C") (pintype "passive"))
      (node (ref "DF11") (pin "C") (pinfunction "C_C") (pintype "passive"))
      (node (ref "DF12") (pin "C") (pinfunction "C_C") (pintype "passive"))
      (node (ref "DF5") (pin "C") (pinfunction "C_C") (pintype "passive"))
      (node (ref "DF6") (pin "C") (pinfunction "C_C") (pintype "passive"))
      (node (ref "DF7") (pin "C") (pinfunction "C_C") (pintype "passive"))
      (node (ref "DF8") (pin "C") (pinfunction "C_C") (pintype "passive"))
      (node (ref "DF9") (pin "C") (pinfunction "C_C") (pintype "passive"))
      (node (ref "DMUTE") (pin "C") (pinfunction "C_C") (pintype "passive"))
      (node (ref "DVOLDOWN") (pin "C") (pinfunction "C_C") (pintype "passive"))
      (node (ref "DVOLUP") (pin "C") (pinfunction "C_C") (pintype "passive"))
      (node (ref "RIGHTCON") (pin "1") (pinfunction "1_1") (pintype "passive"))
    )
    (net (code "67") (name "ROW2") (class "Default")
      (node (ref "D0") (pin "C") (pinfunction "C_C") (pintype "passive"))
      (node (ref "D7") (pin "C") (pinfunction "C_C") (pintype "passive"))
      (node (ref "D8") (pin "C") (pinfunction "C_C") (pintype "passive"))
      (node (ref "D9") (pin "C") (pinfunction "C_C") (pintype "passive"))
      (node (ref "DDASH") (pin "C") (pinfunction "C_C") (pintype "passive"))
      (node (ref "DDELETE") (pin "C") (pinfunction "C_C") (pintype "passive"))
      (node (ref "DEQUALS") (pin "C") (pinfunction "C_C") (pintype "passive"))
      (node (ref "DHOME") (pin "C") (pinfunction "C_C") (pintype "passive"))
      (node (ref "DINSERT") (pin "C") (pinfunction "C_C") (pintype "passive"))
      (node (ref "DPGUP") (pin "C") (pinfunction "C_C") (pintype "passive"))
      (node (ref "RIGHTCON") (pin "11") (pinfunction "11_11") (pintype "passive"))
    )
    (net (code "68") (name "ROW3") (class "Default")
      (node (ref "DBSLASH") (pin "C") (pinfunction "C_C") (pintype "passive"))
      (node (ref "DEND") (pin "C") (pinfunction "C_C") (pintype "passive"))
      (node (ref "DFDEL") (pin "C") (pinfunction "C_C") (pintype "passive"))
      (node (ref "DI") (pin "C") (pinfunction "C_C") (pintype "passive"))
      (node (ref "DLBRACKET") (pin "C") (pinfunction "C_C") (pintype "passive"))
      (node (ref "DO") (pin "C") (pinfunction "C_C") (pintype "passive"))
      (node (ref "DP") (pin "C") (pinfunction "C_C") (pintype "passive"))
      (node (ref "DPGDOWN") (pin "C") (pinfunction "C_C") (pintype "passive"))
      (node (ref "DRBRACKET") (pin "C") (pinfunction "C_C") (pintype "passive"))
      (node (ref "DU") (pin "C") (pinfunction "C_C") (pintype "passive"))
      (node (ref "DY") (pin "C") (pinfunction "C_C") (pintype "passive"))
      (node (ref "RIGHTCON") (pin "9") (pinfunction "9_9") (pintype "passive"))
    )
    (net (code "69") (name "ROW4") (class "Default")
      (node (ref "DH") (pin "C") (pinfunction "C_C") (pintype "passive"))
      (node (ref "DJ") (pin "C") (pinfunction "C_C") (pintype "passive"))
      (node (ref "DK") (pin "C") (pinfunction "C_C") (pintype "passive"))
      (node (ref "DL") (pin "C") (pinfunction "C_C") (pintype "passive"))
      (node (ref "DQUOTE") (pin "C") (pinfunction "C_C") (pintype "passive"))
      (node (ref "DRETURN") (pin "C") (pinfunction "C_C") (pintype "passive"))
      (node (ref "DSEMIC") (pin "C") (pinfunction "C_C") (pintype "passive"))
      (node (ref "RIGHTCON") (pin "7") (pinfunction "7_7") (pintype "passive"))
    )
    (net (code "70") (name "ROW5") (class "Default")
      (node (ref "DCOMMA") (pin "C") (pinfunction "C_C") (pintype "passive"))
      (node (ref "DFSLASH") (pin "C") (pinfunction "C_C") (pintype "passive"))
      (node (ref "DM") (pin "C") (pinfunction "C_C") (pintype "passive"))
      (node (ref "DN") (pin "C") (pinfunction "C_C") (pintype "passive"))
      (node (ref "DPERIOD") (pin "C") (pinfunction "C_C") (pintype "passive"))
      (node (ref "DSHIFT") (pin "C") (pinfunction "C_C") (pintype "passive"))
      (node (ref "DUP") (pin "C") (pinfunction "C_C") (pintype "passive"))
      (node (ref "RIGHTCON") (pin "5") (pinfunction "5_5") (pintype "passive"))
    )
    (net (code "71") (name "ROW6") (class "Default")
      (node (ref "DANY") (pin "C") (pinfunction "C_C") (pintype "passive"))
      (node (ref "DCOMMAND") (pin "C") (pinfunction "C_C") (pintype "passive"))
      (node (ref "DCONTROL") (pin "C") (pinfunction "C_C") (pintype "passive"))
      (node (ref "DDOWN") (pin "C") (pinfunction "C_C") (pintype "passive"))
      (node (ref "DLEFT") (pin "C") (pinfunction "C_C") (pintype "passive"))
      (node (ref "DOPTION") (pin "C") (pinfunction "C_C") (pintype "passive"))
      (node (ref "DRIGHT") (pin "C") (pinfunction "C_C") (pintype "passive"))
      (node (ref "DSPACE") (pin "C") (pinfunction "C_C") (pintype "passive"))
      (node (ref "RIGHTCON") (pin "3") (pinfunction "3_3") (pintype "passive"))
    )
    (net (code "72") (name "unconnected-(RIGHTCON-Pad13)") (class "Default")
      (node (ref "RIGHTCON") (pin "13") (pinfunction "13_13") (pintype "passive"))
    )
    (net (code "73") (name "unconnected-(RIGHTCON-Pad15)") (class "Default")
      (node (ref "RIGHTCON") (pin "15") (pinfunction "15_15") (pintype "passive"))
    )
    (net (code "74") (name "unconnected-(RIGHTCON-Pad17)") (class "Default")
      (node (ref "RIGHTCON") (pin "17") (pinfunction "17_17") (pintype "passive"))
    )
  )
)
